# tarjeta.net
KiCad netlist of a schematic drawn in EAGLE
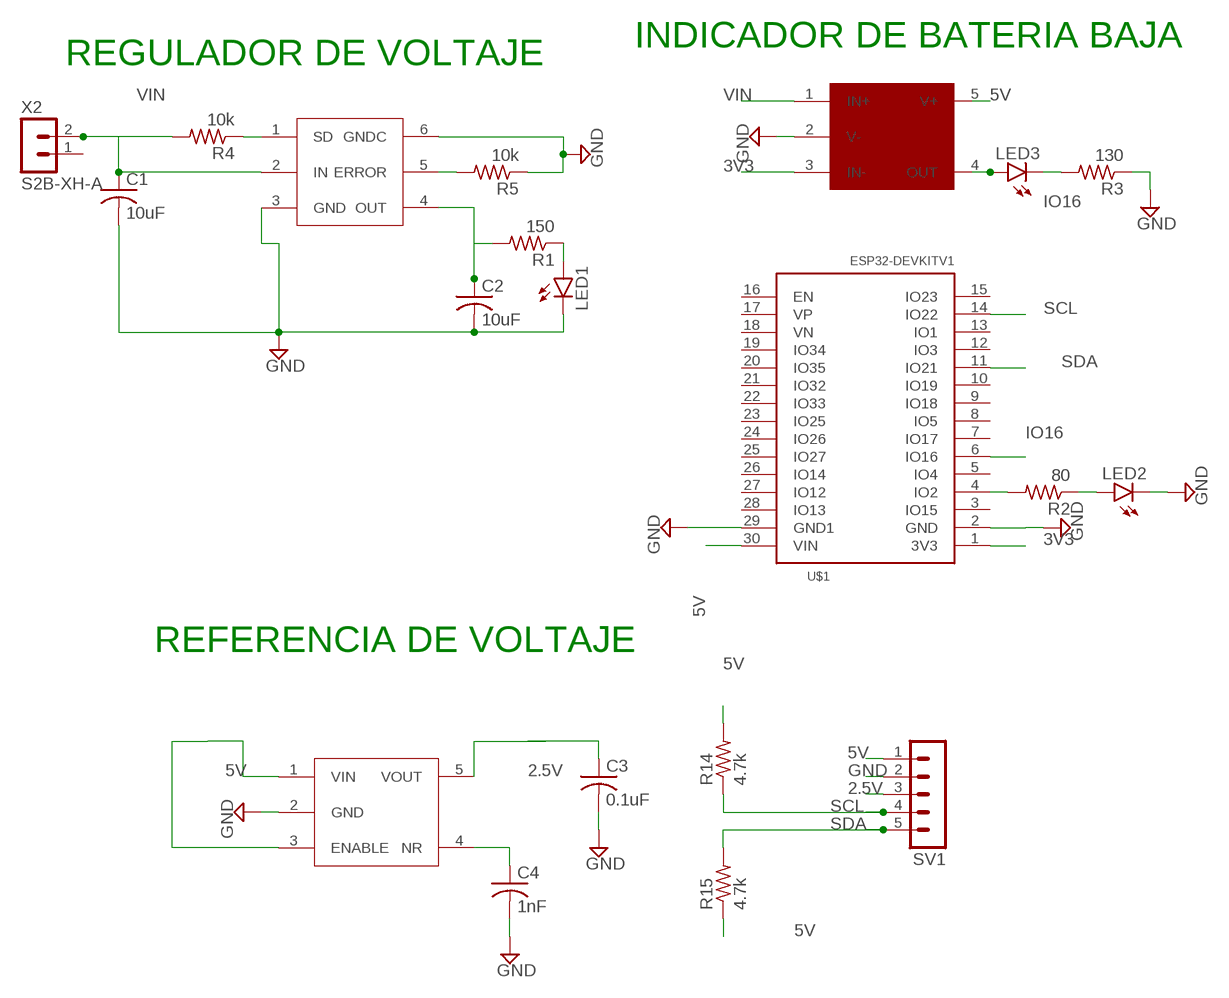
[diagram p0: schematic, sheet 1]

(export (version "E")
  (design (tool "Eeschema 10.0.6"))
  (components
    (comp (ref ".")
      (value "LP3872ES")
      (footprint "eagle-import:TO263-5")
      (libsource (lib "eagle-import") (part "LP3872ES"))
    )
    (comp (ref "C1")
      (value "10uF")
      (footprint "eagle-import:C0603")
      (libsource (lib "eagle-import") (part "C-USC0603"))
    )
    (comp (ref "C2")
      (value "10uF")
      (footprint "eagle-import:C0603")
      (libsource (lib "eagle-import") (part "C-USC0603"))
    )
    (comp (ref "C3")
      (value "0.1uF")
      (footprint "eagle-import:C0603")
      (libsource (lib "eagle-import") (part "C-USC0603"))
    )
    (comp (ref "C4")
      (value "1nF")
      (footprint "eagle-import:C0603")
      (libsource (lib "eagle-import") (part "C-USC0603"))
    )
    (comp (ref "LED1")
      (value "LEDSML0805")
      (footprint "eagle-import:SML0805")
      (libsource (lib "eagle-import") (part "LEDSML0805"))
    )
    (comp (ref "LED2")
      (value "LEDSML0805")
      (footprint "eagle-import:SML0805")
      (libsource (lib "eagle-import") (part "LEDSML0805"))
    )
    (comp (ref "LED3")
      (value "LEDSML0805")
      (footprint "eagle-import:SML0805")
      (libsource (lib "eagle-import") (part "LEDSML0805"))
    )
    (comp (ref "R1")
      (value "150")
      (footprint "eagle-import:R0603")
      (libsource (lib "eagle-import") (part "R-US_R0603"))
    )
    (comp (ref "R2")
      (value "80")
      (footprint "eagle-import:R0603")
      (libsource (lib "eagle-import") (part "R-US_R0603"))
    )
    (comp (ref "R3")
      (value "130")
      (footprint "eagle-import:R0603")
      (libsource (lib "eagle-import") (part "R-US_R0603"))
    )
    (comp (ref "R4")
      (value "10k")
      (footprint "eagle-import:R0603")
      (libsource (lib "eagle-import") (part "R-US_R0603"))
    )
    (comp (ref "R5")
      (value "10k")
      (footprint "eagle-import:R0603")
      (libsource (lib "eagle-import") (part "R-US_R0603"))
    )
    (comp (ref "R14")
      (value "4.7k")
      (footprint "eagle-import:R0603")
      (libsource (lib "eagle-import") (part "R-US_R0603"))
    )
    (comp (ref "R15")
      (value "4.7k")
      (footprint "eagle-import:R0603")
      (libsource (lib "eagle-import") (part "R-US_R0603"))
    )
    (comp (ref "SV1")
      (value "MA05-1")
      (footprint "eagle-import:MA05-1")
      (libsource (lib "eagle-import") (part "MA05-1"))
    )
    (comp (ref "U$1")
      (value "ESP32DEVKITV1")
      (footprint "eagle-import:ESP32-DEVKITV1")
      (libsource (lib "eagle-import") (part "ESP32DEVKITV1"))
    )
    (comp (ref "U$3")
      (value "REG113")
      (footprint "eagle-import:SOT23-5")
      (libsource (lib "eagle-import") (part "REG113"))
    )
    (comp (ref "U$4")
      (value "TL081-5")
      (footprint "eagle-import:SOT23-5")
      (libsource (lib "eagle-import") (part "TL081-5"))
    )
    (comp (ref "X2")
      (value "S2B-XH-A")
      (footprint "eagle-import:S2B-XH-A")
      (libsource (lib "eagle-import") (part "S2B-XH-A"))
    )
  )
  (nets
    (net (code "1") (name "/2.5V") (class "Default")
      (node (ref "C3") (pin "1") (pinfunction "1_1") (pintype "passive"))
      (node (ref "SV1") (pin "3") (pinfunction "3_3") (pintype "passive"))
      (node (ref "U$3") (pin "5") (pinfunction "VOUT_5") (pintype "bidirectional"))
    )
    (net (code "2") (name "/3V3") (class "Default")
      (node (ref "U$1") (pin "1") (pinfunction "3V3_1") (pintype "bidirectional"))
      (node (ref "U$4") (pin "3") (pinfunction "IN-_3") (pintype "bidirectional"))
    )
    (net (code "3") (name "/5V") (class "Default")
      (node (ref "R14") (pin "2") (pinfunction "2_2") (pintype "passive"))
      (node (ref "R15") (pin "1") (pinfunction "1_1") (pintype "passive"))
      (node (ref "SV1") (pin "1") (pinfunction "1_1") (pintype "passive"))
      (node (ref "U$1") (pin "30") (pinfunction "VIN_30") (pintype "bidirectional"))
      (node (ref "U$3") (pin "1") (pinfunction "VIN_1") (pintype "bidirectional"))
      (node (ref "U$3") (pin "3") (pinfunction "ENABLE_3") (pintype "bidirectional"))
      (node (ref "U$4") (pin "5") (pinfunction "V+_5") (pintype "bidirectional"))
    )
    (net (code "4") (name "/IO16") (class "Default")
      (node (ref "LED3") (pin "C") (pinfunction "C_C") (pintype "passive"))
      (node (ref "R3") (pin "2") (pinfunction "2_2") (pintype "passive"))
      (node (ref "U$1") (pin "6") (pinfunction "IO16_6") (pintype "bidirectional"))
    )
    (net (code "5") (name "/SCL") (class "Default")
      (node (ref "R14") (pin "1") (pinfunction "1_1") (pintype "passive"))
      (node (ref "SV1") (pin "4") (pinfunction "4_4") (pintype "passive"))
      (node (ref "U$1") (pin "14") (pinfunction "IO22_14") (pintype "bidirectional"))
    )
    (net (code "6") (name "/SDA") (class "Default")
      (node (ref "R15") (pin "2") (pinfunction "2_2") (pintype "passive"))
      (node (ref "SV1") (pin "5") (pinfunction "5_5") (pintype "passive"))
      (node (ref "U$1") (pin "11") (pinfunction "IO21_11") (pintype "bidirectional"))
    )
    (net (code "7") (name "/VIN") (class "Default")
      (node (ref ".") (pin "2") (pinfunction "IN_2") (pintype "bidirectional"))
      (node (ref "C1") (pin "1") (pinfunction "1_1") (pintype "passive"))
      (node (ref "R4") (pin "2") (pinfunction "2_2") (pintype "passive"))
      (node (ref "U$4") (pin "1") (pinfunction "IN+_1") (pintype "bidirectional"))
      (node (ref "X2") (pin "2") (pinfunction "2_2") (pintype "passive"))
    )
    (net (code "8") (name "GND") (class "Default")
      (node (ref ".") (pin "3") (pinfunction "GND_3") (pintype "bidirectional"))
      (node (ref ".") (pin "6") (pinfunction "GNDC_6") (pintype "bidirectional"))
      (node (ref "C1") (pin "2") (pinfunction "2_2") (pintype "passive"))
      (node (ref "C2") (pin "2") (pinfunction "2_2") (pintype "passive"))
      (node (ref "C3") (pin "2") (pinfunction "2_2") (pintype "passive"))
      (node (ref "C4") (pin "2") (pinfunction "2_2") (pintype "passive"))
      (node (ref "LED1") (pin "C") (pinfunction "C_C") (pintype "passive"))
      (node (ref "LED2") (pin "C") (pinfunction "C_C") (pintype "passive"))
      (node (ref "R3") (pin "1") (pinfunction "1_1") (pintype "passive"))
      (node (ref "R5") (pin "1") (pinfunction "1_1") (pintype "passive"))
      (node (ref "SV1") (pin "2") (pinfunction "2_2") (pintype "passive"))
      (node (ref "U$1") (pin "2") (pinfunction "GND_2") (pintype "bidirectional"))
      (node (ref "U$1") (pin "29") (pinfunction "GND1_29") (pintype "bidirectional"))
      (node (ref "U$3") (pin "2") (pinfunction "GND_2") (pintype "bidirectional"))
      (node (ref "U$4") (pin "2") (pinfunction "V-_2") (pintype "bidirectional"))
    )
    (net (code "9") (name "Net-(.-ERROR)") (class "Default")
      (node (ref ".") (pin "5") (pinfunction "ERROR_5") (pintype "bidirectional"))
      (node (ref "R5") (pin "2") (pinfunction "2_2") (pintype "passive"))
    )
    (net (code "10") (name "Net-(.-OUT)") (class "Default")
      (node (ref ".") (pin "4") (pinfunction "OUT_4") (pintype "bidirectional"))
      (node (ref "C2") (pin "1") (pinfunction "1_1") (pintype "passive"))
      (node (ref "R1") (pin "2") (pinfunction "2_2") (pintype "passive"))
    )
    (net (code "11") (name "Net-(.-SD)") (class "Default")
      (node (ref ".") (pin "1") (pinfunction "SD_1") (pintype "bidirectional"))
      (node (ref "R4") (pin "1") (pinfunction "1_1") (pintype "passive"))
    )
    (net (code "12") (name "Net-(LED1-PadA)") (class "Default")
      (node (ref "LED1") (pin "A") (pinfunction "A_A") (pintype "passive"))
      (node (ref "R1") (pin "1") (pinfunction "1_1") (pintype "passive"))
    )
    (net (code "13") (name "Net-(LED2-PadA)") (class "Default")
      (node (ref "LED2") (pin "A") (pinfunction "A_A") (pintype "passive"))
      (node (ref "R2") (pin "1") (pinfunction "1_1") (pintype "passive"))
    )
    (net (code "14") (name "Net-(U$1-IO2)") (class "Default")
      (node (ref "R2") (pin "2") (pinfunction "2_2") (pintype "passive"))
      (node (ref "U$1") (pin "4") (pinfunction "IO2_4") (pintype "bidirectional"))
    )
    (net (code "15") (name "Net-(U$3-NR)") (class "Default")
      (node (ref "C4") (pin "1") (pinfunction "1_1") (pintype "passive"))
      (node (ref "U$3") (pin "4") (pinfunction "NR_4") (pintype "bidirectional"))
    )
    (net (code "16") (name "Net-(U$4-OUT)") (class "Default")
      (node (ref "LED3") (pin "A") (pinfunction "A_A") (pintype "passive"))
      (node (ref "U$4") (pin "4") (pinfunction "OUT_4") (pintype "bidirectional"))
    )
    (net (code "17") (name "unconnected-(U$1-EN-Pad16)") (class "Default")
      (node (ref "U$1") (pin "16") (pinfunction "EN_16") (pintype "bidirectional"))
    )
    (net (code "18") (name "unconnected-(U$1-IO1-Pad13)") (class "Default")
      (node (ref "U$1") (pin "13") (pinfunction "IO1_13") (pintype "bidirectional"))
    )
    (net (code "19") (name "unconnected-(U$1-IO3-Pad12)") (class "Default")
      (node (ref "U$1") (pin "12") (pinfunction "IO3_12") (pintype "bidirectional"))
    )
    (net (code "20") (name "unconnected-(U$1-IO4-Pad5)") (class "Default")
      (node (ref "U$1") (pin "5") (pinfunction "IO4_5") (pintype "bidirectional"))
    )
    (net (code "21") (name "unconnected-(U$1-IO5-Pad8)") (class "Default")
      (node (ref "U$1") (pin "8") (pinfunction "IO5_8") (pintype "bidirectional"))
    )
    (net (code "22") (name "unconnected-(U$1-IO12-Pad27)") (class "Default")
      (node (ref "U$1") (pin "27") (pinfunction "IO12_27") (pintype "bidirectional"))
    )
    (net (code "23") (name "unconnected-(U$1-IO13-Pad28)") (class "Default")
      (node (ref "U$1") (pin "28") (pinfunction "IO13_28") (pintype "bidirectional"))
    )
    (net (code "24") (name "unconnected-(U$1-IO14-Pad26)") (class "Default")
      (node (ref "U$1") (pin "26") (pinfunction "IO14_26") (pintype "bidirectional"))
    )
    (net (code "25") (name "unconnected-(U$1-IO15-Pad3)") (class "Default")
      (node (ref "U$1") (pin "3") (pinfunction "IO15_3") (pintype "bidirectional"))
    )
    (net (code "26") (name "unconnected-(U$1-IO17-Pad7)") (class "Default")
      (node (ref "U$1") (pin "7") (pinfunction "IO17_7") (pintype "bidirectional"))
    )
    (net (code "27") (name "unconnected-(U$1-IO18-Pad9)") (class "Default")
      (node (ref "U$1") (pin "9") (pinfunction "IO18_9") (pintype "bidirectional"))
    )
    (net (code "28") (name "unconnected-(U$1-IO19-Pad10)") (class "Default")
      (node (ref "U$1") (pin "10") (pinfunction "IO19_10") (pintype "bidirectional"))
    )
    (net (code "29") (name "unconnected-(U$1-IO23-Pad15)") (class "Default")
      (node (ref "U$1") (pin "15") (pinfunction "IO23_15") (pintype "bidirectional"))
    )
    (net (code "30") (name "unconnected-(U$1-IO25-Pad23)") (class "Default")
      (node (ref "U$1") (pin "23") (pinfunction "IO25_23") (pintype "bidirectional"))
    )
    (net (code "31") (name "unconnected-(U$1-IO26-Pad24)") (class "Default")
      (node (ref "U$1") (pin "24") (pinfunction "IO26_24") (pintype "bidirectional"))
    )
    (net (code "32") (name "unconnected-(U$1-IO27-Pad25)") (class "Default")
      (node (ref "U$1") (pin "25") (pinfunction "IO27_25") (pintype "bidirectional"))
    )
    (net (code "33") (name "unconnected-(U$1-IO32-Pad21)") (class "Default")
      (node (ref "U$1") (pin "21") (pinfunction "IO32_21") (pintype "bidirectional"))
    )
    (net (code "34") (name "unconnected-(U$1-IO33-Pad22)") (class "Default")
      (node (ref "U$1") (pin "22") (pinfunction "IO33_22") (pintype "bidirectional"))
    )
    (net (code "35") (name "unconnected-(U$1-IO34-Pad19)") (class "Default")
      (node (ref "U$1") (pin "19") (pinfunction "IO34_19") (pintype "bidirectional"))
    )
    (net (code "36") (name "unconnected-(U$1-IO35-Pad20)") (class "Default")
      (node (ref "U$1") (pin "20") (pinfunction "IO35_20") (pintype "bidirectional"))
    )
    (net (code "37") (name "unconnected-(U$1-VN-Pad18)") (class "Default")
      (node (ref "U$1") (pin "18") (pinfunction "VN_18") (pintype "bidirectional"))
    )
    (net (code "38") (name "unconnected-(U$1-VP-Pad17)") (class "Default")
      (node (ref "U$1") (pin "17") (pinfunction "VP_17") (pintype "bidirectional"))
    )
    (net (code "39") (name "unconnected-(X2-Pad1)") (class "Default")
      (node (ref "X2") (pin "1") (pinfunction "1_1") (pintype "passive"))
    )
  )
)
